# RGB-Controler.net
KiCad netlist of a schematic drawn in EAGLE
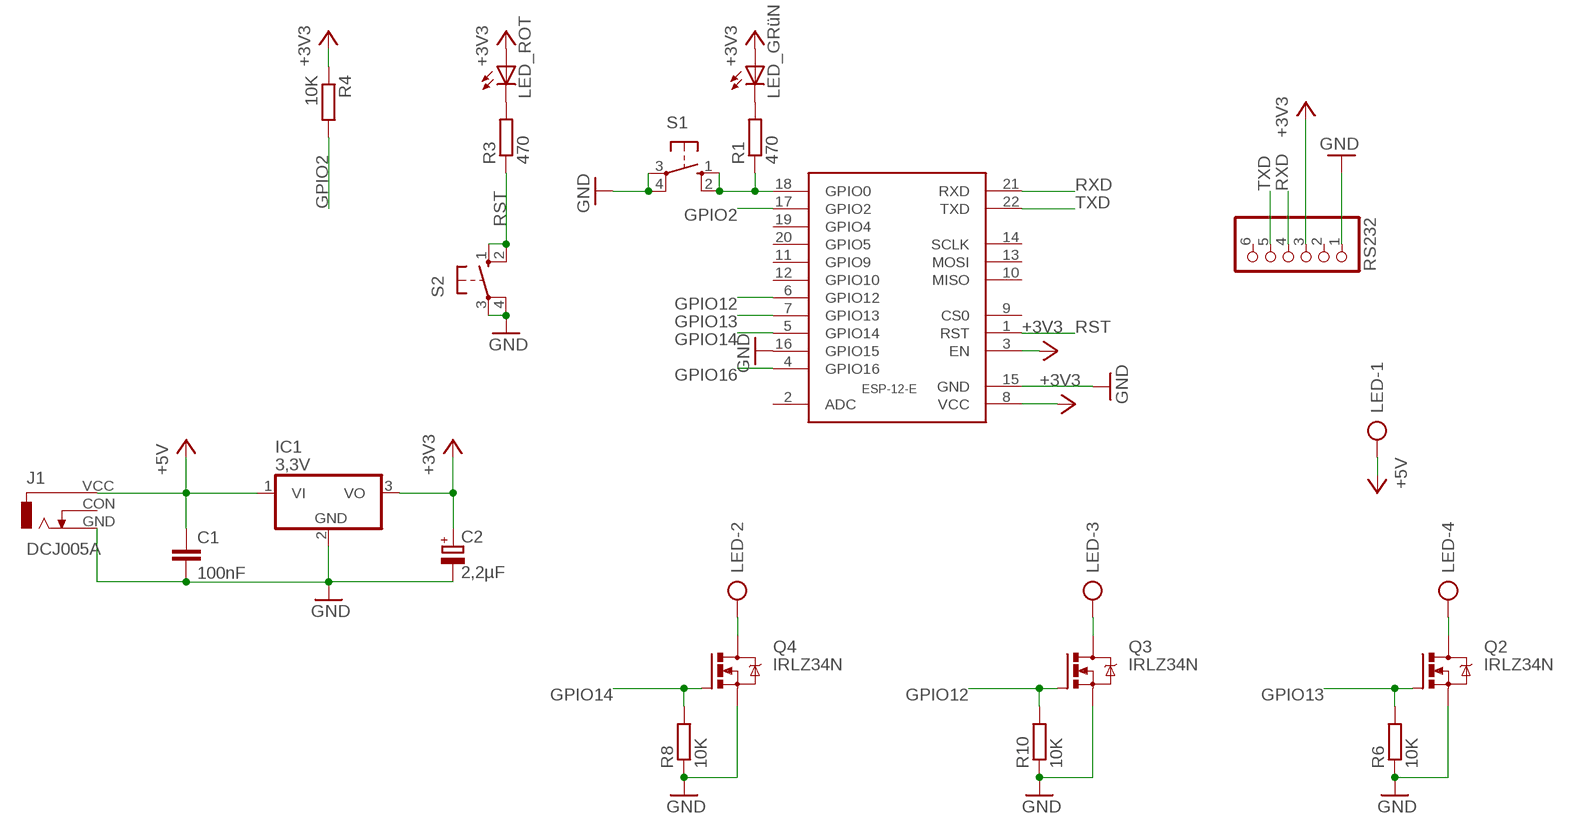
[diagram p0: schematic, sheet 1]

(export (version "E")
  (design (tool "Eeschema 10.0.6"))
  (components
    (comp (ref "C1")
      (value "100nF")
      (footprint "eagle-import:C050-030X075")
      (libsource (lib "eagle-import") (part "C-EU050-030X075"))
    )
    (comp (ref "C2")
      (value "2,2µF")
      (footprint "eagle-import:E2,5-6")
      (libsource (lib "eagle-import") (part "CPOL-EUE2.5-6"))
    )
    (comp (ref "IC1")
      (value "3,3V")
      (footprint "eagle-import:TO220V")
      (libsource (lib "eagle-import") (part "78TV05"))
    )
    (comp (ref "J1")
      (value "DCJ005A")
      (footprint "eagle-import:DC005A")
      (libsource (lib "eagle-import") (part "DCJ005A"))
    )
    (comp (ref "LED")
      (value "AK300/4")
      (footprint "eagle-import:AK300_4")
      (libsource (lib "eagle-import") (part "AK300/4"))
    )
    (comp (ref "LED_GRüN")
      (value "LED5MM")
      (footprint "eagle-import:LED5MM")
      (libsource (lib "eagle-import") (part "LED5MM"))
    )
    (comp (ref "LED_ROT")
      (value "LED5MM")
      (footprint "eagle-import:LED5MM")
      (libsource (lib "eagle-import") (part "LED5MM"))
    )
    (comp (ref "Q2")
      (value "IRLZ34N")
      (footprint "eagle-import:TO220BV")
      (libsource (lib "eagle-import") (part "IRF540"))
    )
    (comp (ref "Q3")
      (value "IRLZ34N")
      (footprint "eagle-import:TO220BV")
      (libsource (lib "eagle-import") (part "IRF540"))
    )
    (comp (ref "Q4")
      (value "IRLZ34N")
      (footprint "eagle-import:TO220BV")
      (libsource (lib "eagle-import") (part "IRF540"))
    )
    (comp (ref "R1")
      (value "470")
      (footprint "eagle-import:0207_10")
      (libsource (lib "eagle-import") (part "R-EU_0207/10"))
    )
    (comp (ref "R3")
      (value "470")
      (footprint "eagle-import:0207_10")
      (libsource (lib "eagle-import") (part "R-EU_0207/10"))
    )
    (comp (ref "R4")
      (value "10K")
      (footprint "eagle-import:0207_10")
      (libsource (lib "eagle-import") (part "R-EU_0207/10"))
    )
    (comp (ref "R6")
      (value "10K")
      (footprint "eagle-import:0207_10")
      (libsource (lib "eagle-import") (part "R-EU_0207/10"))
    )
    (comp (ref "R8")
      (value "10K")
      (footprint "eagle-import:0207_10")
      (libsource (lib "eagle-import") (part "R-EU_0207/10"))
    )
    (comp (ref "R10")
      (value "10K")
      (footprint "eagle-import:0207_10")
      (libsource (lib "eagle-import") (part "R-EU_0207/10"))
    )
    (comp (ref "RS232")
      (value "PINHD-1X6")
      (footprint "eagle-import:1X06")
      (libsource (lib "eagle-import") (part "PINHD-1X6"))
    )
    (comp (ref "S1")
      (value "10-XX")
      (footprint "eagle-import:B3F-10XX")
      (fields (field (name "MPN") "B3F-1000"))
      (libsource (lib "eagle-import") (part "10-XX"))
    )
    (comp (ref "S2")
      (value "10-XX")
      (footprint "eagle-import:B3F-10XX")
      (fields (field (name "MPN") "B3F-1000"))
      (libsource (lib "eagle-import") (part "10-XX"))
    )
    (comp (ref "U$1")
      (value "ESP-12-E")
      (footprint "eagle-import:ESP-12-E")
      (libsource (lib "eagle-import") (part "ESP-12-E"))
    )
  )
  (nets
    (net (code "1") (name "+3V3") (class "Default")
      (node (ref "C2") (pin "+") (pinfunction "+_+") (pintype "passive"))
      (node (ref "IC1") (pin "3") (pinfunction "VO_3") (pintype "passive"))
      (node (ref "LED_GRüN") (pin "A") (pinfunction "A_A") (pintype "passive"))
      (node (ref "LED_ROT") (pin "A") (pinfunction "A_A") (pintype "passive"))
      (node (ref "R4") (pin "1") (pinfunction "1_1") (pintype "passive"))
      (node (ref "RS232") (pin "3") (pinfunction "3_3") (pintype "passive"))
      (node (ref "U$1") (pin "3") (pinfunction "EN_3") (pintype "bidirectional"))
      (node (ref "U$1") (pin "8") (pinfunction "VCC_8") (pintype "power_in"))
    )
    (net (code "2") (name "+5V") (class "Default")
      (node (ref "C1") (pin "1") (pinfunction "1_1") (pintype "passive"))
      (node (ref "IC1") (pin "1") (pinfunction "VI_1") (pintype "input"))
      (node (ref "J1") (pin "VCC") (pinfunction "1_VCC") (pintype "passive"))
      (node (ref "LED") (pin "1") (pinfunction "KL_1") (pintype "passive"))
    )
    (net (code "3") (name "/GPIO2") (class "Default")
      (node (ref "R4") (pin "2") (pinfunction "2_2") (pintype "passive"))
      (node (ref "U$1") (pin "17") (pinfunction "GPIO2_17") (pintype "bidirectional"))
    )
    (net (code "4") (name "/GPIO12") (class "Default")
      (node (ref "Q3") (pin "G") (pinfunction "G_G") (pintype "passive"))
      (node (ref "R10") (pin "2") (pinfunction "2_2") (pintype "passive"))
      (node (ref "U$1") (pin "6") (pinfunction "GPIO12_6") (pintype "bidirectional"))
    )
    (net (code "5") (name "/GPIO13") (class "Default")
      (node (ref "Q2") (pin "G") (pinfunction "G_G") (pintype "passive"))
      (node (ref "R6") (pin "2") (pinfunction "2_2") (pintype "passive"))
      (node (ref "U$1") (pin "7") (pinfunction "GPIO13_7") (pintype "bidirectional"))
    )
    (net (code "6") (name "/GPIO14") (class "Default")
      (node (ref "Q4") (pin "G") (pinfunction "G_G") (pintype "passive"))
      (node (ref "R8") (pin "2") (pinfunction "2_2") (pintype "passive"))
      (node (ref "U$1") (pin "5") (pinfunction "GPIO14_5") (pintype "bidirectional"))
    )
    (net (code "7") (name "/GPIO16") (class "Default")
      (node (ref "U$1") (pin "4") (pinfunction "GPIO16_4") (pintype "bidirectional"))
    )
    (net (code "8") (name "/RST") (class "Default")
      (node (ref "R3") (pin "1") (pinfunction "1_1") (pintype "passive"))
      (node (ref "S2") (pin "1") (pinfunction "S_1") (pintype "passive"))
      (node (ref "S2") (pin "2") (pinfunction "S1_2") (pintype "passive"))
      (node (ref "U$1") (pin "1") (pinfunction "RST_1") (pintype "bidirectional"))
    )
    (net (code "9") (name "/RXD") (class "Default")
      (node (ref "RS232") (pin "4") (pinfunction "4_4") (pintype "passive"))
      (node (ref "U$1") (pin "21") (pinfunction "RXD_21") (pintype "bidirectional"))
    )
    (net (code "10") (name "/TXD") (class "Default")
      (node (ref "RS232") (pin "5") (pinfunction "5_5") (pintype "passive"))
      (node (ref "U$1") (pin "22") (pinfunction "TXD_22") (pintype "bidirectional"))
    )
    (net (code "11") (name "GND") (class "Default")
      (node (ref "C1") (pin "2") (pinfunction "2_2") (pintype "passive"))
      (node (ref "C2") (pin "-") (pinfunction "-_-") (pintype "passive"))
      (node (ref "IC1") (pin "2") (pinfunction "GND_2") (pintype "passive"))
      (node (ref "J1") (pin "GND") (pinfunction "3_GND") (pintype "passive"))
      (node (ref "Q2") (pin "S") (pinfunction "S_S") (pintype "passive"))
      (node (ref "Q3") (pin "S") (pinfunction "S_S") (pintype "passive"))
      (node (ref "Q4") (pin "S") (pinfunction "S_S") (pintype "passive"))
      (node (ref "R10") (pin "1") (pinfunction "1_1") (pintype "passive"))
      (node (ref "R6") (pin "1") (pinfunction "1_1") (pintype "passive"))
      (node (ref "R8") (pin "1") (pinfunction "1_1") (pintype "passive"))
      (node (ref "RS232") (pin "1") (pinfunction "1_1") (pintype "passive"))
      (node (ref "S1") (pin "3") (pinfunction "P_3") (pintype "passive"))
      (node (ref "S1") (pin "4") (pinfunction "P1_4") (pintype "passive"))
      (node (ref "S2") (pin "3") (pinfunction "P_3") (pintype "passive"))
      (node (ref "S2") (pin "4") (pinfunction "P1_4") (pintype "passive"))
      (node (ref "U$1") (pin "15") (pinfunction "GND_15") (pintype "power_in"))
      (node (ref "U$1") (pin "16") (pinfunction "GPIO15_16") (pintype "bidirectional"))
    )
    (net (code "12") (name "Net-(LEDB-KL)") (class "Default")
      (node (ref "LED") (pin "2") (pinfunction "KL_2") (pintype "passive"))
      (node (ref "Q4") (pin "D") (pinfunction "D_D") (pintype "passive"))
    )
    (net (code "13") (name "Net-(LEDC-KL)") (class "Default")
      (node (ref "LED") (pin "3") (pinfunction "KL_3") (pintype "passive"))
      (node (ref "Q3") (pin "D") (pinfunction "D_D") (pintype "passive"))
    )
    (net (code "14") (name "Net-(LEDD-KL)") (class "Default")
      (node (ref "LED") (pin "4") (pinfunction "KL_4") (pintype "passive"))
      (node (ref "Q2") (pin "D") (pinfunction "D_D") (pintype "passive"))
    )
    (net (code "15") (name "Net-(LED_GRüN-C)") (class "Default")
      (node (ref "LED_GRüN") (pin "K") (pinfunction "C_K") (pintype "passive"))
      (node (ref "R1") (pin "2") (pinfunction "2_2") (pintype "passive"))
    )
    (net (code "16") (name "Net-(LED_ROT-C)") (class "Default")
      (node (ref "LED_ROT") (pin "K") (pinfunction "C_K") (pintype "passive"))
      (node (ref "R3") (pin "2") (pinfunction "2_2") (pintype "passive"))
    )
    (net (code "17") (name "Net-(S1-S)") (class "Default")
      (node (ref "R1") (pin "1") (pinfunction "1_1") (pintype "passive"))
      (node (ref "S1") (pin "1") (pinfunction "S_1") (pintype "passive"))
      (node (ref "S1") (pin "2") (pinfunction "S1_2") (pintype "passive"))
      (node (ref "U$1") (pin "18") (pinfunction "GPIO0_18") (pintype "bidirectional"))
    )
    (net (code "18") (name "unconnected-(J1-2-PadCON)") (class "Default")
      (node (ref "J1") (pin "CON") (pinfunction "2_CON") (pintype "passive"))
    )
    (net (code "19") (name "unconnected-(RS232-Pad2)") (class "Default")
      (node (ref "RS232") (pin "2") (pinfunction "2_2") (pintype "passive"))
    )
    (net (code "20") (name "unconnected-(RS232-Pad6)") (class "Default")
      (node (ref "RS232") (pin "6") (pinfunction "6_6") (pintype "passive"))
    )
    (net (code "21") (name "unconnected-(U$1-ADC-Pad2)") (class "Default")
      (node (ref "U$1") (pin "2") (pinfunction "ADC_2") (pintype "bidirectional"))
    )
    (net (code "22") (name "unconnected-(U$1-CS0-Pad9)") (class "Default")
      (node (ref "U$1") (pin "9") (pinfunction "CS0_9") (pintype "bidirectional"))
    )
    (net (code "23") (name "unconnected-(U$1-GPIO4-Pad19)") (class "Default")
      (node (ref "U$1") (pin "19") (pinfunction "GPIO4_19") (pintype "bidirectional"))
    )
    (net (code "24") (name "unconnected-(U$1-GPIO5-Pad20)") (class "Default")
      (node (ref "U$1") (pin "20") (pinfunction "GPIO5_20") (pintype "bidirectional"))
    )
    (net (code "25") (name "unconnected-(U$1-GPIO9-Pad11)") (class "Default")
      (node (ref "U$1") (pin "11") (pinfunction "GPIO9_11") (pintype "bidirectional"))
    )
    (net (code "26") (name "unconnected-(U$1-GPIO10-Pad12)") (class "Default")
      (node (ref "U$1") (pin "12") (pinfunction "GPIO10_12") (pintype "bidirectional"))
    )
    (net (code "27") (name "unconnected-(U$1-MISO-Pad10)") (class "Default")
      (node (ref "U$1") (pin "10") (pinfunction "MISO_10") (pintype "bidirectional"))
    )
    (net (code "28") (name "unconnected-(U$1-MOSI-Pad13)") (class "Default")
      (node (ref "U$1") (pin "13") (pinfunction "MOSI_13") (pintype "bidirectional"))
    )
    (net (code "29") (name "unconnected-(U$1-SCLK-Pad14)") (class "Default")
      (node (ref "U$1") (pin "14") (pinfunction "SCLK_14") (pintype "bidirectional"))
    )
  )
)
